# SparkFun-Qwiic-Mini-Human-Presence-Senso.net
KiCad netlist of a schematic drawn in EAGLE
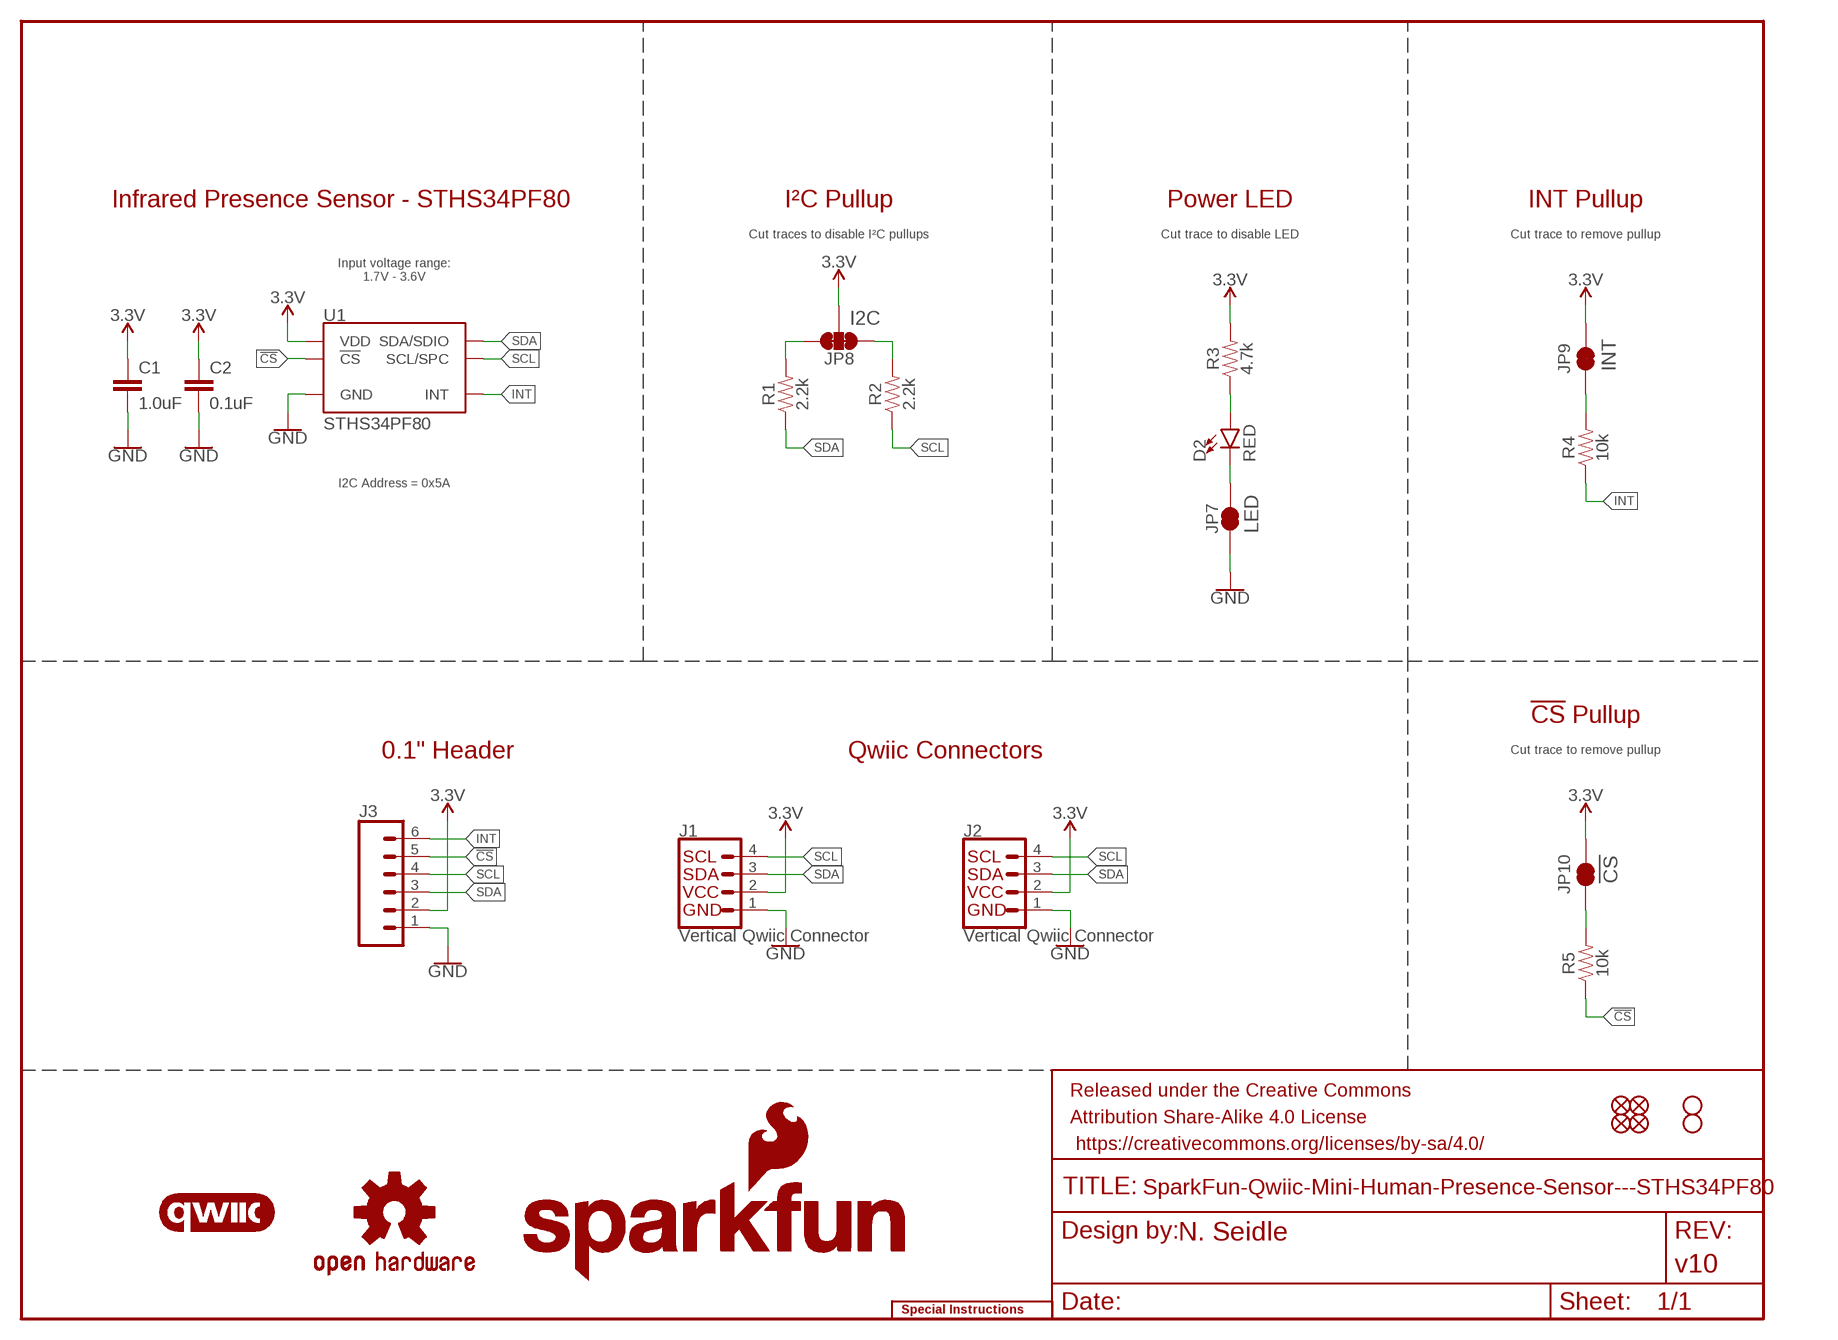
[diagram p0: schematic, sheet 1]

(export (version "E")
  (design (tool "Eeschema 10.0.6"))
  (components
    (comp (ref "C1")
      (value "1.0uF")
      (footprint "eagle-import:0603")
      (libsource (lib "eagle-import") (part "1.0UF-0603-16V-10%"))
    )
    (comp (ref "C2")
      (value "0.1uF")
      (footprint "eagle-import:0603")
      (libsource (lib "eagle-import") (part "0.1UF-0603-25V-(+80/-20%)"))
    )
    (comp (ref "D2")
      (value "RED")
      (footprint "eagle-import:LED-0603")
      (libsource (lib "eagle-import") (part "LED-RED_0603-KB"))
    )
    (comp (ref "FRAME1")
      (value "FRAME-LETTER")
      (footprint "eagle-import:CREATIVE_COMMONS")
      (fields (field (name "DESIGNER") "N. Seidle") (field (name "REV") "v10"))
      (libsource (lib "eagle-import") (part "FRAME-LETTER"))
    )
    (comp (ref "J1")
      (value "Vertical Qwiic Connector")
      (footprint "eagle-import:JST04_1MM_VERT")
      (libsource (lib "eagle-import") (part "QWIIC_CONNECTOR"))
    )
    (comp (ref "J2")
      (value "Vertical Qwiic Connector")
      (footprint "eagle-import:JST04_1MM_VERT")
      (libsource (lib "eagle-import") (part "QWIIC_CONNECTOR"))
    )
    (comp (ref "J3")
      (value "CONN_06NO_SILK_FEMALE_PTH")
      (footprint "eagle-import:1X06_NO_SILK")
      (libsource (lib "eagle-import") (part "CONN_06NO_SILK_FEMALE_PTH"))
    )
    (comp (ref "JP1")
      (value "FIDUCIALUFIDUCIAL")
      (footprint "eagle-import:FIDUCIAL-MICRO")
      (libsource (lib "eagle-import") (part "FIDUCIALUFIDUCIAL"))
    )
    (comp (ref "JP2")
      (value "FIDUCIALUFIDUCIAL")
      (footprint "eagle-import:FIDUCIAL-MICRO")
      (libsource (lib "eagle-import") (part "FIDUCIALUFIDUCIAL"))
    )
    (comp (ref "JP3")
      (value "STAND-OFF")
      (footprint "eagle-import:STAND-OFF")
      (libsource (lib "eagle-import") (part "STAND-OFF"))
    )
    (comp (ref "JP4")
      (value "STAND-OFF")
      (footprint "eagle-import:STAND-OFF")
      (libsource (lib "eagle-import") (part "STAND-OFF"))
    )
    (comp (ref "JP5")
      (value "FIDUCIALUFIDUCIAL")
      (footprint "eagle-import:FIDUCIAL-MICRO")
      (libsource (lib "eagle-import") (part "FIDUCIALUFIDUCIAL"))
    )
    (comp (ref "JP6")
      (value "FIDUCIALUFIDUCIAL")
      (footprint "eagle-import:FIDUCIAL-MICRO")
      (libsource (lib "eagle-import") (part "FIDUCIALUFIDUCIAL"))
    )
    (comp (ref "JP7")
      (value "JUMPER-SMT_2_NC_TRACE_SILK")
      (footprint "eagle-import:SMT-JUMPER_2_NC_TRACE_SILK")
      (libsource (lib "eagle-import") (part "JUMPER-SMT_2_NC_TRACE_SILK"))
    )
    (comp (ref "JP8")
      (value "JUMPER-SMT_3_2-NC_TRACE_SILK")
      (footprint "eagle-import:SMT-JUMPER_3_2-NC_TRACE_SILK")
      (libsource (lib "eagle-import") (part "JUMPER-SMT_3_2-NC_TRACE_SILK"))
    )
    (comp (ref "JP9")
      (value "JUMPER-SMT_2_NC_TRACE_SILK")
      (footprint "eagle-import:SMT-JUMPER_2_NC_TRACE_SILK")
      (libsource (lib "eagle-import") (part "JUMPER-SMT_2_NC_TRACE_SILK"))
    )
    (comp (ref "JP10")
      (value "JUMPER-SMT_2_NC_TRACE_SILK")
      (footprint "eagle-import:SMT-JUMPER_2_NC_TRACE_SILK")
      (libsource (lib "eagle-import") (part "JUMPER-SMT_2_NC_TRACE_SILK"))
    )
    (comp (ref "LOGO1")
      (value "OSHW-LOGOS")
      (footprint "eagle-import:OSHW-LOGO-S")
      (libsource (lib "eagle-import") (part "OSHW-LOGOS"))
    )
    (comp (ref "LOGO2")
      (value "SFE_LOGO_NAME_FLAME7_MM")
      (footprint "eagle-import:SFE_LOGO_NAME_FLAME_7MM")
      (libsource (lib "eagle-import") (part "SFE_LOGO_NAME_FLAME7_MM"))
    )
    (comp (ref "LOGO3")
      (value "QWIIC_LOGO_CONNECTOR")
      (footprint "eagle-import:QWIIC_5.5MM")
      (libsource (lib "eagle-import") (part "QWIIC_LOGO_CONNECTOR"))
    )
    (comp (ref "LOGO4")
      (value "SFE_LOGO_NAME5_MM")
      (footprint "eagle-import:SFE_LOGO_NAME_5MM")
      (libsource (lib "eagle-import") (part "SFE_LOGO_NAME5_MM"))
    )
    (comp (ref "LOGO5")
      (value "SPECIAL_INSTRUCTIONS-ORDERING")
      (footprint "eagle-import:ORDERING_INSTRUCTIONS")
      (libsource (lib "eagle-import") (part "SPECIAL_INSTRUCTIONS-ORDERING"))
    )
    (comp (ref "LOGO6")
      (value "SFE_LOGO_FLAME.1_INCH")
      (footprint "eagle-import:SFE_LOGO_FLAME_.1")
      (libsource (lib "eagle-import") (part "SFE_LOGO_FLAME.1_INCH"))
    )
    (comp (ref "R1")
      (value "2.2k")
      (footprint "eagle-import:0603")
      (libsource (lib "eagle-import") (part "2.2KOHM-0603-1/10W-1%"))
    )
    (comp (ref "R2")
      (value "2.2k")
      (footprint "eagle-import:0603")
      (libsource (lib "eagle-import") (part "2.2KOHM-0603-1/10W-1%"))
    )
    (comp (ref "R3")
      (value "4.7k")
      (footprint "eagle-import:0603")
      (libsource (lib "eagle-import") (part "4.7KOHM-0603-1/10W-1%"))
    )
    (comp (ref "R4")
      (value "10k")
      (footprint "eagle-import:0603")
      (libsource (lib "eagle-import") (part "10KOHM-0603-1/10W-1%"))
    )
    (comp (ref "R5")
      (value "10k")
      (footprint "eagle-import:0603")
      (libsource (lib "eagle-import") (part "10KOHM-0603-1/10W-1%"))
    )
    (comp (ref "U1")
      (value "STHS34PF80")
      (footprint "eagle-import:OLGA-10L")
      (fields (field (name "PROD_ID") "IC-19626"))
      (libsource (lib "eagle-import") (part "STHS34PF80"))
    )
  )
  (nets
    (net (code "1") (name "/~{CS}") (class "Default")
      (node (ref "J3") (pin "5") (pinfunction "5_5") (pintype "passive"))
      (node (ref "R5") (pin "1") (pinfunction "1_1") (pintype "passive"))
      (node (ref "U1") (pin "3") (pinfunction "~{CS}_3") (pintype "input"))
    )
    (net (code "2") (name "3.3V") (class "Default")
      (node (ref "C1") (pin "1") (pinfunction "1_1") (pintype "passive"))
      (node (ref "C2") (pin "1") (pinfunction "1_1") (pintype "passive"))
      (node (ref "J1") (pin "2") (pinfunction "2_2") (pintype "power_in"))
      (node (ref "J2") (pin "2") (pinfunction "2_2") (pintype "power_in"))
      (node (ref "J3") (pin "2") (pinfunction "2_2") (pintype "passive"))
      (node (ref "JP10") (pin "2") (pinfunction "2_2") (pintype "passive"))
      (node (ref "JP8") (pin "2") (pinfunction "2_2") (pintype "passive"))
      (node (ref "JP9") (pin "2") (pinfunction "2_2") (pintype "passive"))
      (node (ref "R3") (pin "2") (pinfunction "2_2") (pintype "passive"))
      (node (ref "U1") (pin "6") (pinfunction "VDD_6") (pintype "power_in"))
      (node (ref "U1") (pin "9") (pinfunction "VDD_9") (pintype "power_in"))
    )
    (net (code "3") (name "GND") (class "Default")
      (node (ref "C1") (pin "2") (pinfunction "2_2") (pintype "passive"))
      (node (ref "C2") (pin "2") (pinfunction "2_2") (pintype "passive"))
      (node (ref "J1") (pin "1") (pinfunction "1_1") (pintype "power_in"))
      (node (ref "J2") (pin "1") (pinfunction "1_1") (pintype "power_in"))
      (node (ref "J3") (pin "1") (pinfunction "1_1") (pintype "passive"))
      (node (ref "JP7") (pin "1") (pinfunction "1_1") (pintype "passive"))
      (node (ref "U1") (pin "2") (pinfunction "GND_2") (pintype "power_in"))
      (node (ref "U1") (pin "7") (pinfunction "GND_7") (pintype "power_in"))
      (node (ref "U1") (pin "8") (pinfunction "GND_8") (pintype "power_in"))
    )
    (net (code "4") (name "INT") (class "Default")
      (node (ref "J3") (pin "6") (pinfunction "6_6") (pintype "passive"))
      (node (ref "R4") (pin "1") (pinfunction "1_1") (pintype "passive"))
      (node (ref "U1") (pin "10") (pinfunction "INT_10") (pintype "output"))
    )
    (net (code "5") (name "Net-(D2-PadA)") (class "Default")
      (node (ref "D2") (pin "A") (pinfunction "A_A") (pintype "passive"))
      (node (ref "R3") (pin "1") (pinfunction "1_1") (pintype "passive"))
    )
    (net (code "6") (name "Net-(D2-PadC)") (class "Default")
      (node (ref "D2") (pin "C") (pinfunction "C_C") (pintype "passive"))
      (node (ref "JP7") (pin "2") (pinfunction "2_2") (pintype "passive"))
    )
    (net (code "7") (name "Net-(JP8-Pad1)") (class "Default")
      (node (ref "JP8") (pin "1") (pinfunction "1_1") (pintype "passive"))
      (node (ref "R2") (pin "2") (pinfunction "2_2") (pintype "passive"))
    )
    (net (code "8") (name "Net-(JP8-Pad3)") (class "Default")
      (node (ref "JP8") (pin "3") (pinfunction "3_3") (pintype "passive"))
      (node (ref "R1") (pin "2") (pinfunction "2_2") (pintype "passive"))
    )
    (net (code "9") (name "Net-(JP9-Pad1)") (class "Default")
      (node (ref "JP9") (pin "1") (pinfunction "1_1") (pintype "passive"))
      (node (ref "R4") (pin "2") (pinfunction "2_2") (pintype "passive"))
    )
    (net (code "10") (name "Net-(JP10-Pad1)") (class "Default")
      (node (ref "JP10") (pin "1") (pinfunction "1_1") (pintype "passive"))
      (node (ref "R5") (pin "2") (pinfunction "2_2") (pintype "passive"))
    )
    (net (code "11") (name "SCL") (class "Default")
      (node (ref "J1") (pin "4") (pinfunction "4_4") (pintype "passive"))
      (node (ref "J2") (pin "4") (pinfunction "4_4") (pintype "passive"))
      (node (ref "J3") (pin "4") (pinfunction "4_4") (pintype "passive"))
      (node (ref "R2") (pin "1") (pinfunction "1_1") (pintype "passive"))
      (node (ref "U1") (pin "1") (pinfunction "SCL/SPC_1") (pintype "bidirectional"))
    )
    (net (code "12") (name "SDA") (class "Default")
      (node (ref "J1") (pin "3") (pinfunction "3_3") (pintype "passive"))
      (node (ref "J2") (pin "3") (pinfunction "3_3") (pintype "passive"))
      (node (ref "J3") (pin "3") (pinfunction "3_3") (pintype "passive"))
      (node (ref "R1") (pin "1") (pinfunction "1_1") (pintype "passive"))
      (node (ref "U1") (pin "4") (pinfunction "SDA/SDIO_4") (pintype "bidirectional"))
    )
  )
)
